# systems-controller.net
KiCad netlist of a schematic drawn in EAGLE
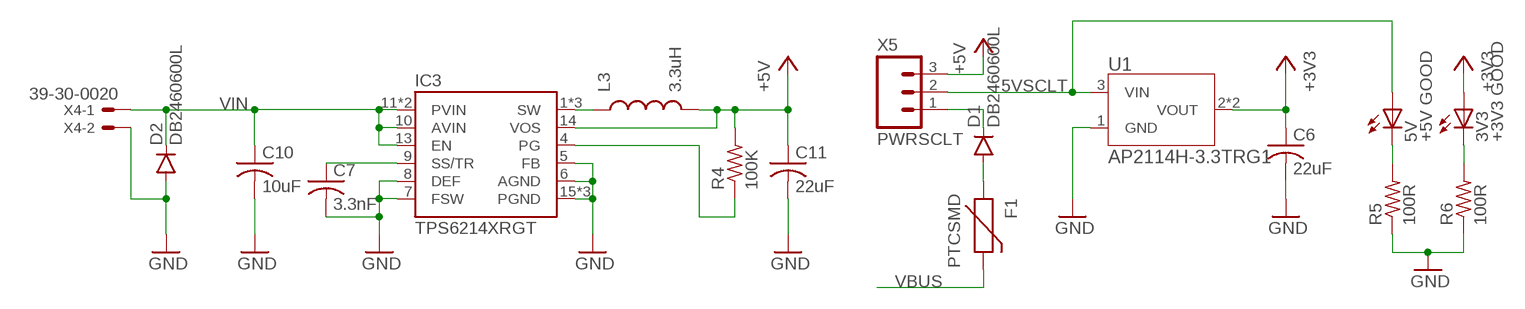
[diagram p0: schematic, sheet 1]
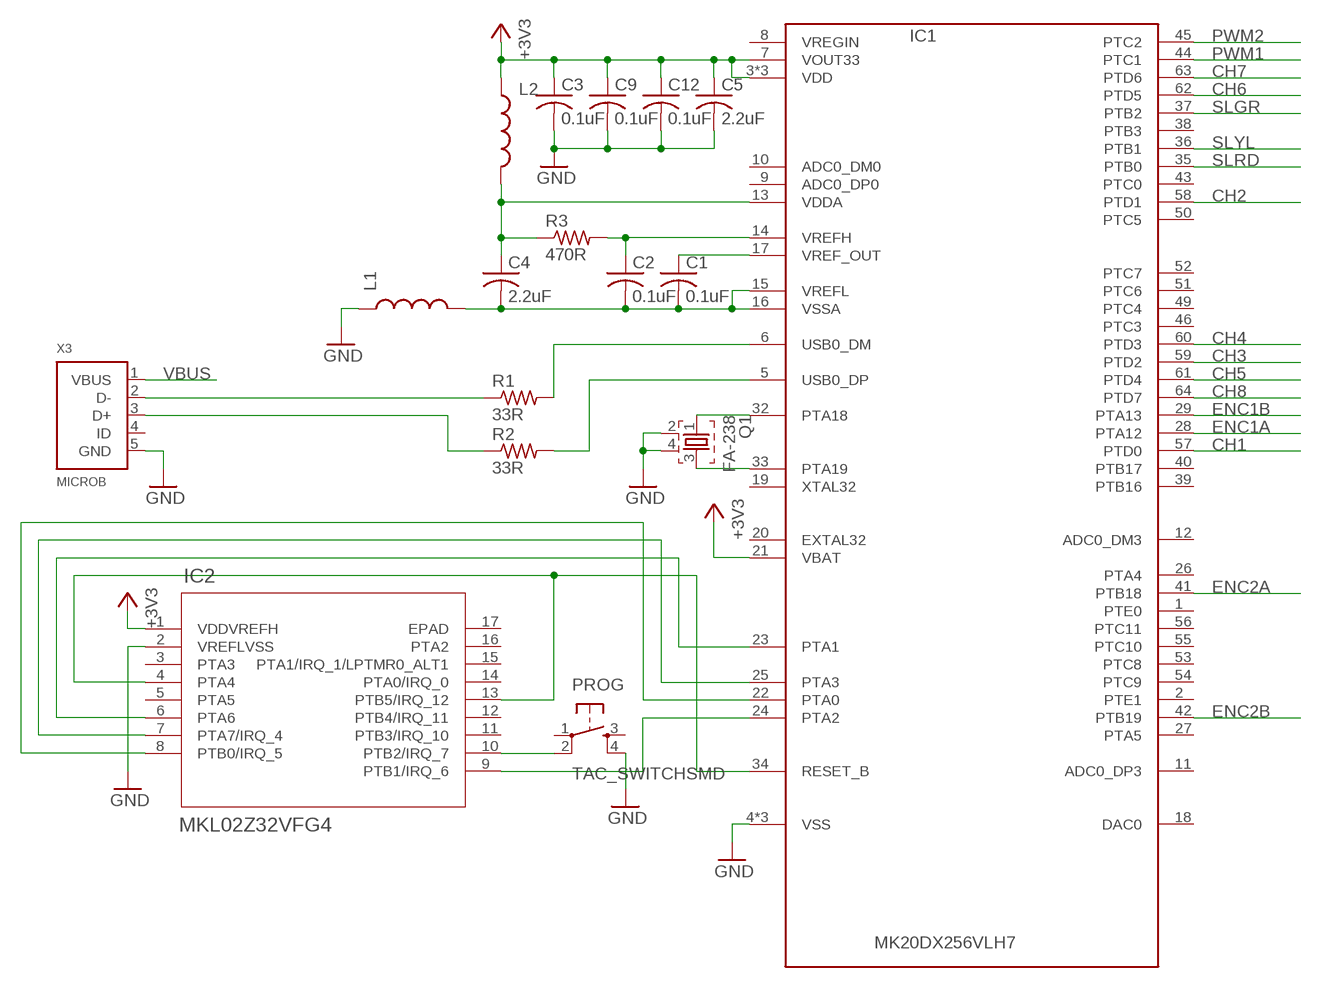
[diagram p1: schematic, sheet 2]
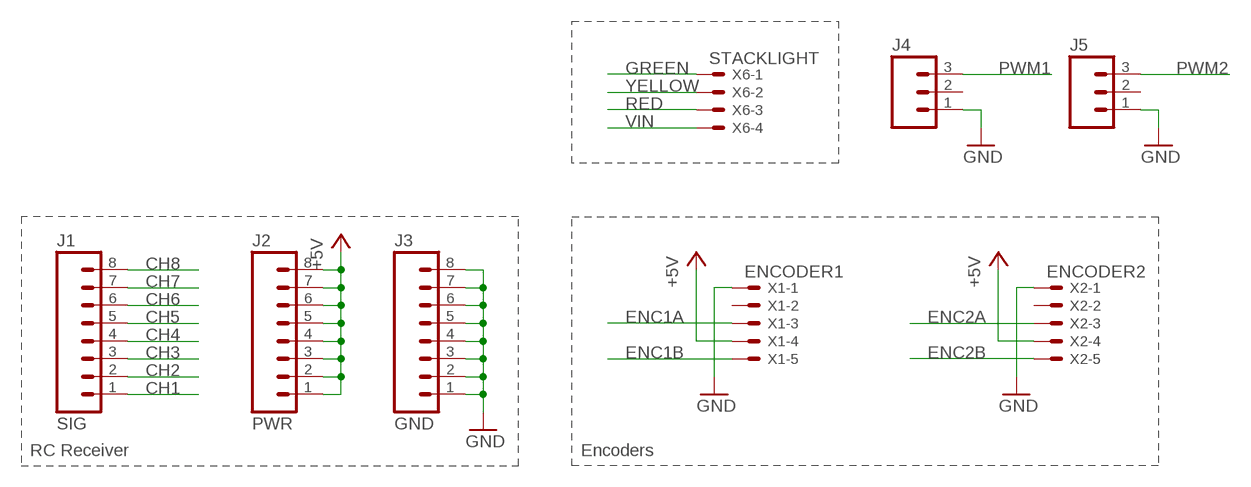
[diagram p2: schematic, sheet 3]
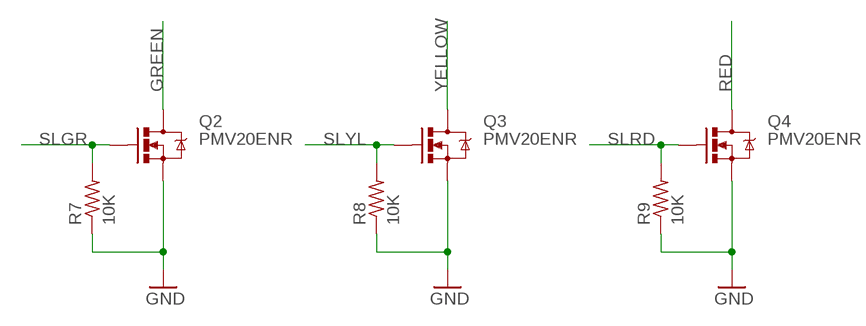
[diagram p3: schematic, sheet 4]

(export (version "E")
  (design (tool "Eeschema 10.0.6"))
  (components
    (comp (ref "3V3")
      (value "+3V3 GOOD")
      (footprint "eagle-import:SML0603")
      (libsource (lib "eagle-import") (part "LEDSML0603"))
    )
    (comp (ref "5V")
      (value "+5V GOOD")
      (footprint "eagle-import:SML0603")
      (libsource (lib "eagle-import") (part "LEDSML0603"))
    )
    (comp (ref "C6")
      (value "22uF")
      (footprint "eagle-import:C0805K")
      (libsource (lib "eagle-import") (part "C-USC0805K"))
    )
    (comp (ref "C7")
      (value "3.3nF")
      (footprint "eagle-import:C0603K")
      (libsource (lib "eagle-import") (part "C-USC0603K"))
    )
    (comp (ref "C10")
      (value "10uF")
      (footprint "eagle-import:C0805K")
      (libsource (lib "eagle-import") (part "C-USC0805K"))
    )
    (comp (ref "C11")
      (value "22uF")
      (footprint "eagle-import:C0805K")
      (libsource (lib "eagle-import") (part "C-USC0805K"))
    )
    (comp (ref "D1")
      (value "DB2460600L")
      (footprint "eagle-import:SOD-128")
      (libsource (lib "eagle-import") (part "DIODESOD128"))
    )
    (comp (ref "D2")
      (value "DB2460600L")
      (footprint "eagle-import:SOD-128")
      (libsource (lib "eagle-import") (part "DIODESOD128"))
    )
    (comp (ref "F1")
      (value "PTCSMD")
      (footprint "eagle-import:PTC-1206")
      (libsource (lib "eagle-import") (part "PTCSMD"))
    )
    (comp (ref "IC3")
      (value "TPS6214XRGT")
      (footprint "eagle-import:16-VQFN")
      (libsource (lib "eagle-import") (part "TPS6214XRGT"))
    )
    (comp (ref "L3")
      (value "3.3uH")
      (footprint "eagle-import:SRN5020")
      (libsource (lib "eagle-import") (part "INDUCTOR-SRN5020"))
    )
    (comp (ref "R4")
      (value "100K")
      (footprint "eagle-import:R0603")
      (libsource (lib "eagle-import") (part "R-US_R0603"))
    )
    (comp (ref "R5")
      (value "100R")
      (footprint "eagle-import:R0603")
      (libsource (lib "eagle-import") (part "R-US_R0603"))
    )
    (comp (ref "R6")
      (value "100R")
      (footprint "eagle-import:R0603")
      (libsource (lib "eagle-import") (part "R-US_R0603"))
    )
    (comp (ref "U1")
      (value "AP2114H-3.3TRG1")
      (footprint "eagle-import:SOT-223")
      (fields (field (name "MANUFACTURER_PART_NUMBER") "ap2114h-3.3trg1"))
      (libsource (lib "eagle-import") (part "AP2114H-3.3TRG1"))
    )
    (comp (ref "X4")
      (value "39-30-0020")
      (footprint "eagle-import:39-30-0020")
      (libsource (lib "eagle-import") (part "39-30-0020"))
    )
    (comp (ref "X5")
      (value "PWRSCLT")
      (footprint "eagle-import:1X03")
      (libsource (lib "eagle-import") (part "M03PTH"))
    )
    (comp (ref "J1")
      (value "SIG")
      (footprint "eagle-import:1X08_ROUND")
      (libsource (lib "eagle-import") (part "M08"))
    )
    (comp (ref "J2")
      (value "PWR")
      (footprint "eagle-import:1X08_ROUND")
      (libsource (lib "eagle-import") (part "M08"))
    )
    (comp (ref "J3")
      (value "GND")
      (footprint "eagle-import:1X08_ROUND")
      (libsource (lib "eagle-import") (part "M08"))
    )
    (comp (ref "J4")
      (value "M03PTH")
      (footprint "eagle-import:1X03")
      (libsource (lib "eagle-import") (part "M03PTH"))
    )
    (comp (ref "J5")
      (value "M03PTH")
      (footprint "eagle-import:1X03")
      (libsource (lib "eagle-import") (part "M03PTH"))
    )
    (comp (ref "X1")
      (value "ENCODER1")
      (footprint "eagle-import:70553-05")
      (libsource (lib "eagle-import") (part "C-GRID-05-70553"))
    )
    (comp (ref "X2")
      (value "ENCODER2")
      (footprint "eagle-import:70553-05")
      (libsource (lib "eagle-import") (part "C-GRID-05-70553"))
    )
    (comp (ref "X6")
      (value "STACKLIGHT")
      (footprint "eagle-import:70553-04")
      (libsource (lib "eagle-import") (part "C-GRID-04-70553"))
    )
    (comp (ref "Q2")
      (value "PMV20ENR")
      (footprint "eagle-import:SOT23-3")
      (libsource (lib "eagle-import") (part "MOSFET-NCHANNELAO3404A"))
    )
    (comp (ref "Q3")
      (value "PMV20ENR")
      (footprint "eagle-import:SOT23-3")
      (libsource (lib "eagle-import") (part "MOSFET-NCHANNELAO3404A"))
    )
    (comp (ref "Q4")
      (value "PMV20ENR")
      (footprint "eagle-import:SOT23-3")
      (libsource (lib "eagle-import") (part "MOSFET-NCHANNELAO3404A"))
    )
    (comp (ref "R7")
      (value "10K")
      (footprint "eagle-import:R0603")
      (libsource (lib "eagle-import") (part "R-US_R0603"))
    )
    (comp (ref "R8")
      (value "10K")
      (footprint "eagle-import:R0603")
      (libsource (lib "eagle-import") (part "R-US_R0603"))
    )
    (comp (ref "R9")
      (value "10K")
      (footprint "eagle-import:R0603")
      (libsource (lib "eagle-import") (part "R-US_R0603"))
    )
    (comp (ref "C1")
      (value "0.1uF")
      (footprint "eagle-import:C0603K")
      (libsource (lib "eagle-import") (part "C-USC0603K"))
    )
    (comp (ref "C2")
      (value "0.1uF")
      (footprint "eagle-import:C0603K")
      (libsource (lib "eagle-import") (part "C-USC0603K"))
    )
    (comp (ref "C3")
      (value "0.1uF")
      (footprint "eagle-import:C0603K")
      (libsource (lib "eagle-import") (part "C-USC0603K"))
    )
    (comp (ref "C4")
      (value "2.2uF")
      (footprint "eagle-import:C0603K")
      (libsource (lib "eagle-import") (part "C-USC0603K"))
    )
    (comp (ref "C5")
      (value "2.2uF")
      (footprint "eagle-import:C0603K")
      (libsource (lib "eagle-import") (part "C-USC0603K"))
    )
    (comp (ref "C9")
      (value "0.1uF")
      (footprint "eagle-import:C0603K")
      (libsource (lib "eagle-import") (part "C-USC0603K"))
    )
    (comp (ref "C12")
      (value "0.1uF")
      (footprint "eagle-import:C0603K")
      (libsource (lib "eagle-import") (part "C-USC0603K"))
    )
    (comp (ref "IC1")
      (value "MK20DX256VLH7")
      (footprint "eagle-import:MK20DX256VLH7")
      (libsource (lib "eagle-import") (part "MK20DX256VLH7"))
    )
    (comp (ref "IC2")
      (value "MKL02Z32VFG4")
      (footprint "eagle-import:QFN-16_3X3X0.65")
      (fields (field (name "MANUFACTURER_PART_NUMBER") "mkl02z32vfg4"))
      (libsource (lib "eagle-import") (part "MKL02Z32VFG4"))
    )
    (comp (ref "L1")
      (value "INDUCTOR30OHM,1.8A")
      (footprint "eagle-import:0603")
      (libsource (lib "eagle-import") (part "INDUCTOR30OHM,1.8A"))
    )
    (comp (ref "L2")
      (value "INDUCTOR30OHM,1.8A")
      (footprint "eagle-import:0603")
      (libsource (lib "eagle-import") (part "INDUCTOR30OHM,1.8A"))
    )
    (comp (ref "PROG")
      (value "TAC_SWITCHSMD")
      (footprint "eagle-import:TACTILE-SWITCH-SMD")
      (libsource (lib "eagle-import") (part "TAC_SWITCHSMD"))
    )
    (comp (ref "Q1")
      (value "FA-238")
      (footprint "eagle-import:FA-238")
      (libsource (lib "eagle-import") (part "FA-238"))
    )
    (comp (ref "R1")
      (value "33R")
      (footprint "eagle-import:R0603")
      (libsource (lib "eagle-import") (part "R-US_R0603"))
    )
    (comp (ref "R2")
      (value "33R")
      (footprint "eagle-import:R0603")
      (libsource (lib "eagle-import") (part "R-US_R0603"))
    )
    (comp (ref "R3")
      (value "470R")
      (footprint "eagle-import:R0603")
      (libsource (lib "eagle-import") (part "R-US_R0603"))
    )
    (comp (ref "X3")
      (value "MICROB")
      (footprint "eagle-import:10118192")
      (libsource (lib "eagle-import") (part "MICROB"))
    )
  )
  (nets
    (net (code "1") (name "+3V3") (class "Default")
      (node (ref "3V3") (pin "A") (pinfunction "A_A") (pintype "passive"))
      (node (ref "C12") (pin "1") (pinfunction "1_1") (pintype "passive"))
      (node (ref "C3") (pin "1") (pinfunction "1_1") (pintype "passive"))
      (node (ref "C5") (pin "1") (pinfunction "1_1") (pintype "passive"))
      (node (ref "C6") (pin "1") (pinfunction "1_1") (pintype "passive"))
      (node (ref "C9") (pin "1") (pinfunction "1_1") (pintype "passive"))
      (node (ref "IC1") (pin "21") (pinfunction "VBAT_21") (pintype "bidirectional"))
      (node (ref "IC1") (pin "3") (pinfunction "VDD_3") (pintype "bidirectional"))
      (node (ref "IC1") (pin "30") (pinfunction "VDD_30") (pintype "bidirectional"))
      (node (ref "IC1") (pin "48") (pinfunction "VDD_48") (pintype "bidirectional"))
      (node (ref "IC1") (pin "7") (pinfunction "VOUT33_7") (pintype "bidirectional"))
      (node (ref "IC2") (pin "1") (pinfunction "VDDVREFH_1") (pintype "power_in"))
      (node (ref "L2") (pin "1") (pinfunction "1_1") (pintype "passive"))
      (node (ref "U1") (pin "2") (pinfunction "VOUT_2") (pintype "output"))
      (node (ref "U1") (pin "4") (pinfunction "VOUT_4") (pintype "output"))
    )
    (net (code "2") (name "+5V") (class "Default")
      (node (ref "C11") (pin "1") (pinfunction "1_1") (pintype "passive"))
      (node (ref "IC3") (pin "14") (pinfunction "VOS_14") (pintype "input"))
      (node (ref "J2") (pin "1") (pinfunction "1_1") (pintype "passive"))
      (node (ref "J2") (pin "2") (pinfunction "2_2") (pintype "passive"))
      (node (ref "J2") (pin "3") (pinfunction "3_3") (pintype "passive"))
      (node (ref "J2") (pin "4") (pinfunction "4_4") (pintype "passive"))
      (node (ref "J2") (pin "5") (pinfunction "5_5") (pintype "passive"))
      (node (ref "J2") (pin "6") (pinfunction "6_6") (pintype "passive"))
      (node (ref "J2") (pin "7") (pinfunction "7_7") (pintype "passive"))
      (node (ref "J2") (pin "8") (pinfunction "8_8") (pintype "passive"))
      (node (ref "L3") (pin "2") (pinfunction "2_2") (pintype "passive"))
      (node (ref "R4") (pin "2") (pinfunction "2_2") (pintype "passive"))
      (node (ref "X1") (pin "4") (pinfunction "S_4") (pintype "passive"))
      (node (ref "X2") (pin "4") (pinfunction "S_4") (pintype "passive"))
      (node (ref "X5") (pin "3") (pinfunction "3_3") (pintype "passive"))
    )
    (net (code "3") (name "5VSCLT") (class "Default")
      (node (ref "5V") (pin "A") (pinfunction "A_A") (pintype "passive"))
      (node (ref "U1") (pin "3") (pinfunction "VIN_3") (pintype "input"))
      (node (ref "X5") (pin "2") (pinfunction "2_2") (pintype "passive"))
    )
    (net (code "4") (name "CH1") (class "Default")
      (node (ref "IC1") (pin "57") (pinfunction "PTD0_57") (pintype "bidirectional"))
      (node (ref "J1") (pin "1") (pinfunction "1_1") (pintype "passive"))
    )
    (net (code "5") (name "CH2") (class "Default")
      (node (ref "IC1") (pin "58") (pinfunction "PTD1_58") (pintype "bidirectional"))
      (node (ref "J1") (pin "2") (pinfunction "2_2") (pintype "passive"))
    )
    (net (code "6") (name "CH3") (class "Default")
      (node (ref "IC1") (pin "59") (pinfunction "PTD2_59") (pintype "bidirectional"))
      (node (ref "J1") (pin "3") (pinfunction "3_3") (pintype "passive"))
    )
    (net (code "7") (name "CH4") (class "Default")
      (node (ref "IC1") (pin "60") (pinfunction "PTD3_60") (pintype "bidirectional"))
      (node (ref "J1") (pin "4") (pinfunction "4_4") (pintype "passive"))
    )
    (net (code "8") (name "CH5") (class "Default")
      (node (ref "IC1") (pin "61") (pinfunction "PTD4_61") (pintype "bidirectional"))
      (node (ref "J1") (pin "5") (pinfunction "5_5") (pintype "passive"))
    )
    (net (code "9") (name "CH6") (class "Default")
      (node (ref "IC1") (pin "62") (pinfunction "PTD5_62") (pintype "bidirectional"))
      (node (ref "J1") (pin "6") (pinfunction "6_6") (pintype "passive"))
    )
    (net (code "10") (name "CH7") (class "Default")
      (node (ref "IC1") (pin "63") (pinfunction "PTD6_63") (pintype "bidirectional"))
      (node (ref "J1") (pin "7") (pinfunction "7_7") (pintype "passive"))
    )
    (net (code "11") (name "CH8") (class "Default")
      (node (ref "IC1") (pin "64") (pinfunction "PTD7_64") (pintype "bidirectional"))
      (node (ref "J1") (pin "8") (pinfunction "8_8") (pintype "passive"))
    )
    (net (code "12") (name "ENC1A") (class "Default")
      (node (ref "IC1") (pin "28") (pinfunction "PTA12_28") (pintype "bidirectional"))
      (node (ref "X1") (pin "3") (pinfunction "S_3") (pintype "passive"))
    )
    (net (code "13") (name "ENC1B") (class "Default")
      (node (ref "IC1") (pin "29") (pinfunction "PTA13_29") (pintype "bidirectional"))
      (node (ref "X1") (pin "5") (pinfunction "S_5") (pintype "passive"))
    )
    (net (code "14") (name "ENC2A") (class "Default")
      (node (ref "IC1") (pin "41") (pinfunction "PTB18_41") (pintype "bidirectional"))
      (node (ref "X2") (pin "3") (pinfunction "S_3") (pintype "passive"))
    )
    (net (code "15") (name "ENC2B") (class "Default")
      (node (ref "IC1") (pin "42") (pinfunction "PTB19_42") (pintype "bidirectional"))
      (node (ref "X2") (pin "5") (pinfunction "S_5") (pintype "passive"))
    )
    (net (code "16") (name "GND") (class "Default")
      (node (ref "C10") (pin "2") (pinfunction "2_2") (pintype "passive"))
      (node (ref "C11") (pin "2") (pinfunction "2_2") (pintype "passive"))
      (node (ref "C12") (pin "2") (pinfunction "2_2") (pintype "passive"))
      (node (ref "C3") (pin "2") (pinfunction "2_2") (pintype "passive"))
      (node (ref "C5") (pin "2") (pinfunction "2_2") (pintype "passive"))
      (node (ref "C6") (pin "2") (pinfunction "2_2") (pintype "passive"))
      (node (ref "C7") (pin "2") (pinfunction "2_2") (pintype "passive"))
      (node (ref "C9") (pin "2") (pinfunction "2_2") (pintype "passive"))
      (node (ref "D2") (pin "A") (pinfunction "A_A") (pintype "passive"))
      (node (ref "IC1") (pin "31") (pinfunction "VSS_31") (pintype "bidirectional"))
      (node (ref "IC1") (pin "4") (pinfunction "VSS_4") (pintype "bidirectional"))
      (node (ref "IC1") (pin "47") (pinfunction "VSS_47") (pintype "bidirectional"))
      (node (ref "IC2") (pin "2") (pinfunction "VREFLVSS_2") (pintype "power_in"))
      (node (ref "IC3") (pin "15") (pinfunction "PGND_15") (pintype "power_in"))
      (node (ref "IC3") (pin "16") (pinfunction "PGND_16") (pintype "power_in"))
      (node (ref "IC3") (pin "5") (pinfunction "FB_5") (pintype "input"))
      (node (ref "IC3") (pin "6") (pinfunction "AGND_6") (pintype "input"))
      (node (ref "IC3") (pin "7") (pinfunction "FSW_7") (pintype "input"))
      (node (ref "IC3") (pin "8") (pinfunction "DEF_8") (pintype "input"))
      (node (ref "IC3") (pin "PAD") (pinfunction "PGND_PAD") (pintype "power_in"))
      (node (ref "J3") (pin "1") (pinfunction "1_1") (pintype "passive"))
      (node (ref "J3") (pin "2") (pinfunction "2_2") (pintype "passive"))
      (node (ref "J3") (pin "3") (pinfunction "3_3") (pintype "passive"))
      (node (ref "J3") (pin "4") (pinfunction "4_4") (pintype "passive"))
      (node (ref "J3") (pin "5") (pinfunction "5_5") (pintype "passive"))
      (node (ref "J3") (pin "6") (pinfunction "6_6") (pintype "passive"))
      (node (ref "J3") (pin "7") (pinfunction "7_7") (pintype "passive"))
      (node (ref "J3") (pin "8") (pinfunction "8_8") (pintype "passive"))
      (node (ref "J4") (pin "1") (pinfunction "1_1") (pintype "passive"))
      (node (ref "J5") (pin "1") (pinfunction "1_1") (pintype "passive"))
      (node (ref "L1") (pin "1") (pinfunction "1_1") (pintype "passive"))
      (node (ref "PROG") (pin "4") (pinfunction "4_4") (pintype "passive"))
      (node (ref "Q1") (pin "2") (pinfunction "2_2") (pintype "passive"))
      (node (ref "Q1") (pin "4") (pinfunction "4_4") (pintype "passive"))
      (node (ref "Q2") (pin "2") (pinfunction "S_2") (pintype "passive"))
      (node (ref "Q3") (pin "2") (pinfunction "S_2") (pintype "passive"))
      (node (ref "Q4") (pin "2") (pinfunction "S_2") (pintype "passive"))
      (node (ref "R5") (pin "1") (pinfunction "1_1") (pintype "passive"))
      (node (ref "R6") (pin "1") (pinfunction "1_1") (pintype "passive"))
      (node (ref "R7") (pin "1") (pinfunction "1_1") (pintype "passive"))
      (node (ref "R8") (pin "1") (pinfunction "1_1") (pintype "passive"))
      (node (ref "R9") (pin "1") (pinfunction "1_1") (pintype "passive"))
      (node (ref "U1") (pin "1") (pinfunction "GND_1") (pintype "power_in"))
      (node (ref "X1") (pin "1") (pinfunction "S_1") (pintype "passive"))
      (node (ref "X2") (pin "1") (pinfunction "S_1") (pintype "passive"))
      (node (ref "X3") (pin "5") (pinfunction "GND_5") (pintype "bidirectional"))
      (node (ref "X4") (pin "2") (pinfunction "S_2") (pintype "passive"))
    )
    (net (code "17") (name "GREEN") (class "Default")
      (node (ref "Q2") (pin "3") (pinfunction "D_3") (pintype "passive"))
      (node (ref "X6") (pin "1") (pinfunction "S_1") (pintype "passive"))
    )
    (net (code "18") (name "Net-(3V3-PadC)") (class "Default")
      (node (ref "3V3") (pin "C") (pinfunction "C_C") (pintype "passive"))
      (node (ref "R6") (pin "2") (pinfunction "2_2") (pintype "passive"))
    )
    (net (code "19") (name "Net-(5V-PadC)") (class "Default")
      (node (ref "5V") (pin "C") (pinfunction "C_C") (pintype "passive"))
      (node (ref "R5") (pin "2") (pinfunction "2_2") (pintype "passive"))
    )
    (net (code "20") (name "Net-(D1-PadA)") (class "Default")
      (node (ref "D1") (pin "A") (pinfunction "A_A") (pintype "passive"))
      (node (ref "F1") (pin "1") (pinfunction "1_1") (pintype "bidirectional"))
    )
    (net (code "21") (name "Net-(D1-PadC)") (class "Default")
      (node (ref "D1") (pin "C") (pinfunction "C_C") (pintype "passive"))
      (node (ref "X5") (pin "1") (pinfunction "1_1") (pintype "passive"))
    )
    (net (code "22") (name "Net-(IC1-PTA0)") (class "Default")
      (node (ref "IC1") (pin "22") (pinfunction "PTA0_22") (pintype "bidirectional"))
      (node (ref "IC2") (pin "8") (pinfunction "PTB0/IRQ_5_8") (pintype "bidirectional"))
    )
    (net (code "23") (name "Net-(IC1-PTA1)") (class "Default")
      (node (ref "IC1") (pin "23") (pinfunction "PTA1_23") (pintype "bidirectional"))
      (node (ref "IC2") (pin "6") (pinfunction "PTA6_6") (pintype "bidirectional"))
    )
    (net (code "24") (name "Net-(IC1-PTA2)") (class "Default")
      (node (ref "IC1") (pin "24") (pinfunction "PTA2_24") (pintype "bidirectional"))
      (node (ref "IC2") (pin "9") (pinfunction "PTB1/IRQ_6_9") (pintype "bidirectional"))
    )
    (net (code "25") (name "Net-(IC1-PTA3)") (class "Default")
      (node (ref "IC1") (pin "25") (pinfunction "PTA3_25") (pintype "bidirectional"))
      (node (ref "IC2") (pin "7") (pinfunction "PTA7/IRQ_4_7") (pintype "bidirectional"))
    )
    (net (code "26") (name "Net-(IC1-PTA18)") (class "Default")
      (node (ref "IC1") (pin "32") (pinfunction "PTA18_32") (pintype "bidirectional"))
      (node (ref "Q1") (pin "1") (pinfunction "1_1") (pintype "passive"))
    )
    (net (code "27") (name "Net-(IC1-PTA19)") (class "Default")
      (node (ref "IC1") (pin "33") (pinfunction "PTA19_33") (pintype "bidirectional"))
      (node (ref "Q1") (pin "3") (pinfunction "3_3") (pintype "passive"))
    )
    (net (code "28") (name "Net-(IC1-RESET_B)") (class "Default")
      (node (ref "IC1") (pin "34") (pinfunction "RESET_B_34") (pintype "bidirectional"))
      (node (ref "IC2") (pin "13") (pinfunction "PTB5/IRQ_12_13") (pintype "bidirectional"))
      (node (ref "IC2") (pin "4") (pinfunction "PTA4_4") (pintype "bidirectional"))
    )
    (net (code "29") (name "Net-(IC1-USB0_DM)") (class "Default")
      (node (ref "IC1") (pin "6") (pinfunction "USB0_DM_6") (pintype "bidirectional"))
      (node (ref "R1") (pin "2") (pinfunction "2_2") (pintype "passive"))
    )
    (net (code "30") (name "Net-(IC1-USB0_DP)") (class "Default")
      (node (ref "IC1") (pin "5") (pinfunction "USB0_DP_5") (pintype "bidirectional"))
      (node (ref "R2") (pin "2") (pinfunction "2_2") (pintype "passive"))
    )
    (net (code "31") (name "Net-(IC1-VDDA)") (class "Default")
      (node (ref "C4") (pin "1") (pinfunction "1_1") (pintype "passive"))
      (node (ref "IC1") (pin "13") (pinfunction "VDDA_13") (pintype "bidirectional"))
      (node (ref "L2") (pin "2") (pinfunction "2_2") (pintype "passive"))
      (node (ref "R3") (pin "1") (pinfunction "1_1") (pintype "passive"))
    )
    (net (code "32") (name "Net-(IC1-VREFH)") (class "Default")
      (node (ref "C2") (pin "1") (pinfunction "1_1") (pintype "passive"))
      (node (ref "IC1") (pin "14") (pinfunction "VREFH_14") (pintype "bidirectional"))
      (node (ref "R3") (pin "2") (pinfunction "2_2") (pintype "passive"))
    )
    (net (code "33") (name "Net-(IC1-VREFL)") (class "Default")
      (node (ref "C1") (pin "2") (pinfunction "2_2") (pintype "passive"))
      (node (ref "C2") (pin "2") (pinfunction "2_2") (pintype "passive"))
      (node (ref "C4") (pin "2") (pinfunction "2_2") (pintype "passive"))
      (node (ref "IC1") (pin "15") (pinfunction "VREFL_15") (pintype "bidirectional"))
      (node (ref "IC1") (pin "16") (pinfunction "VSSA_16") (pintype "bidirectional"))
      (node (ref "L1") (pin "2") (pinfunction "2_2") (pintype "passive"))
    )
    (net (code "34") (name "Net-(IC1-VREF_OUT)") (class "Default")
      (node (ref "C1") (pin "1") (pinfunction "1_1") (pintype "passive"))
      (node (ref "IC1") (pin "17") (pinfunction "VREF_OUT_17") (pintype "bidirectional"))
    )
    (net (code "35") (name "Net-(IC2-PTB2{slash}IRQ_7)") (class "Default")
      (node (ref "IC2") (pin "10") (pinfunction "PTB2/IRQ_7_10") (pintype "bidirectional"))
      (node (ref "PROG") (pin "2") (pinfunction "2_2") (pintype "passive"))
    )
    (net (code "36") (name "Net-(IC3-PG)") (class "Default")
      (node (ref "IC3") (pin "4") (pinfunction "PG_4") (pintype "output"))
      (node (ref "R4") (pin "1") (pinfunction "1_1") (pintype "passive"))
    )
    (net (code "37") (name "Net-(IC3-SS{slash}TR)") (class "Default")
      (node (ref "C7") (pin "1") (pinfunction "1_1") (pintype "passive"))
      (node (ref "IC3") (pin "9") (pinfunction "SS/TR_9") (pintype "input"))
    )
    (net (code "38") (name "Net-(IC3-SW-Pad1)") (class "Default")
      (node (ref "IC3") (pin "1") (pinfunction "SW_1") (pintype "output"))
      (node (ref "IC3") (pin "2") (pinfunction "SW_2") (pintype "output"))
      (node (ref "IC3") (pin "3") (pinfunction "SW_3") (pintype "output"))
      (node (ref "L3") (pin "1") (pinfunction "1_1") (pintype "passive"))
    )
    (net (code "39") (name "Net-(X3-D+)") (class "Default")
      (node (ref "R2") (pin "1") (pinfunction "1_1") (pintype "passive"))
      (node (ref "X3") (pin "3") (pinfunction "D+_3") (pintype "bidirectional"))
    )
    (net (code "40") (name "Net-(X3-D-)") (class "Default")
      (node (ref "R1") (pin "1") (pinfunction "1_1") (pintype "passive"))
      (node (ref "X3") (pin "2") (pinfunction "D-_2") (pintype "bidirectional"))
    )
    (net (code "41") (name "PWM1") (class "Default")
      (node (ref "IC1") (pin "44") (pinfunction "PTC1_44") (pintype "bidirectional"))
      (node (ref "J4") (pin "3") (pinfunction "3_3") (pintype "passive"))
    )
    (net (code "42") (name "PWM2") (class "Default")
      (node (ref "IC1") (pin "45") (pinfunction "PTC2_45") (pintype "bidirectional"))
      (node (ref "J5") (pin "3") (pinfunction "3_3") (pintype "passive"))
    )
    (net (code "43") (name "RED") (class "Default")
      (node (ref "Q4") (pin "3") (pinfunction "D_3") (pintype "passive"))
      (node (ref "X6") (pin "3") (pinfunction "S_3") (pintype "passive"))
    )
    (net (code "44") (name "SLGR") (class "Default")
      (node (ref "IC1") (pin "37") (pinfunction "PTB2_37") (pintype "bidirectional"))
      (node (ref "Q2") (pin "1") (pinfunction "G_1") (pintype "passive"))
      (node (ref "R7") (pin "2") (pinfunction "2_2") (pintype "passive"))
    )
    (net (code "45") (name "SLRD") (class "Default")
      (node (ref "IC1") (pin "35") (pinfunction "PTB0_35") (pintype "bidirectional"))
      (node (ref "Q4") (pin "1") (pinfunction "G_1") (pintype "passive"))
      (node (ref "R9") (pin "2") (pinfunction "2_2") (pintype "passive"))
    )
    (net (code "46") (name "SLYL") (class "Default")
      (node (ref "IC1") (pin "36") (pinfunction "PTB1_36") (pintype "bidirectional"))
      (node (ref "Q3") (pin "1") (pinfunction "G_1") (pintype "passive"))
      (node (ref "R8") (pin "2") (pinfunction "2_2") (pintype "passive"))
    )
    (net (code "47") (name "VBUS") (class "Default")
      (node (ref "F1") (pin "2") (pinfunction "2_2") (pintype "bidirectional"))
      (node (ref "X3") (pin "1") (pinfunction "VBUS_1") (pintype "bidirectional"))
    )
    (net (code "48") (name "VIN") (class "Default")
      (node (ref "C10") (pin "1") (pinfunction "1_1") (pintype "passive"))
      (node (ref "D2") (pin "C") (pinfunction "C_C") (pintype "passive"))
      (node (ref "IC3") (pin "10") (pinfunction "AVIN_10") (pintype "input"))
      (node (ref "IC3") (pin "11") (pinfunction "PVIN_11") (pintype "input"))
      (node (ref "IC3") (pin "12") (pinfunction "PVIN_12") (pintype "input"))
      (node (ref "IC3") (pin "13") (pinfunction "EN_13") (pintype "input"))
      (node (ref "X4") (pin "1") (pinfunction "S_1") (pintype "passive"))
      (node (ref "X6") (pin "4") (pinfunction "S_4") (pintype "passive"))
    )
    (net (code "49") (name "YELLOW") (class "Default")
      (node (ref "Q3") (pin "3") (pinfunction "D_3") (pintype "passive"))
      (node (ref "X6") (pin "2") (pinfunction "S_2") (pintype "passive"))
    )
    (net (code "50") (name "unconnected-(IC1-ADC0_DM0-Pad10)") (class "Default")
      (node (ref "IC1") (pin "10") (pinfunction "ADC0_DM0_10") (pintype "bidirectional"))
    )
    (net (code "51") (name "unconnected-(IC1-ADC0_DM3-Pad12)") (class "Default")
      (node (ref "IC1") (pin "12") (pinfunction "ADC0_DM3_12") (pintype "bidirectional"))
    )
    (net (code "52") (name "unconnected-(IC1-ADC0_DP0-Pad9)") (class "Default")
      (node (ref "IC1") (pin "9") (pinfunction "ADC0_DP0_9") (pintype "bidirectional"))
    )
    (net (code "53") (name "unconnected-(IC1-ADC0_DP3-Pad11)") (class "Default")
      (node (ref "IC1") (pin "11") (pinfunction "ADC0_DP3_11") (pintype "bidirectional"))
    )
    (net (code "54") (name "unconnected-(IC1-DAC0-Pad18)") (class "Default")
      (node (ref "IC1") (pin "18") (pinfunction "DAC0_18") (pintype "bidirectional"))
    )
    (net (code "55") (name "unconnected-(IC1-EXTAL32-Pad20)") (class "Default")
      (node (ref "IC1") (pin "20") (pinfunction "EXTAL32_20") (pintype "bidirectional"))
    )
    (net (code "56") (name "unconnected-(IC1-PTA4-Pad26)") (class "Default")
      (node (ref "IC1") (pin "26") (pinfunction "PTA4_26") (pintype "bidirectional"))
    )
    (net (code "57") (name "unconnected-(IC1-PTA5-Pad27)") (class "Default")
      (node (ref "IC1") (pin "27") (pinfunction "PTA5_27") (pintype "bidirectional"))
    )
    (net (code "58") (name "unconnected-(IC1-PTB3-Pad38)") (class "Default")
      (node (ref "IC1") (pin "38") (pinfunction "PTB3_38") (pintype "bidirectional"))
    )
    (net (code "59") (name "unconnected-(IC1-PTB16-Pad39)") (class "Default")
      (node (ref "IC1") (pin "39") (pinfunction "PTB16_39") (pintype "bidirectional"))
    )
    (net (code "60") (name "unconnected-(IC1-PTB17-Pad40)") (class "Default")
      (node (ref "IC1") (pin "40") (pinfunction "PTB17_40") (pintype "bidirectional"))
    )
    (net (code "61") (name "unconnected-(IC1-PTC0-Pad43)") (class "Default")
      (node (ref "IC1") (pin "43") (pinfunction "PTC0_43") (pintype "bidirectional"))
    )
    (net (code "62") (name "unconnected-(IC1-PTC3-Pad46)") (class "Default")
      (node (ref "IC1") (pin "46") (pinfunction "PTC3_46") (pintype "bidirectional"))
    )
    (net (code "63") (name "unconnected-(IC1-PTC4-Pad49)") (class "Default")
      (node (ref "IC1") (pin "49") (pinfunction "PTC4_49") (pintype "bidirectional"))
    )
    (net (code "64") (name "unconnected-(IC1-PTC5-Pad50)") (class "Default")
      (node (ref "IC1") (pin "50") (pinfunction "PTC5_50") (pintype "bidirectional"))
    )
    (net (code "65") (name "unconnected-(IC1-PTC6-Pad51)") (class "Default")
      (node (ref "IC1") (pin "51") (pinfunction "PTC6_51") (pintype "bidirectional"))
    )
    (net (code "66") (name "unconnected-(IC1-PTC7-Pad52)") (class "Default")
      (node (ref "IC1") (pin "52") (pinfunction "PTC7_52") (pintype "bidirectional"))
    )
    (net (code "67") (name "unconnected-(IC1-PTC8-Pad53)") (class "Default")
      (node (ref "IC1") (pin "53") (pinfunction "PTC8_53") (pintype "bidirectional"))
    )
    (net (code "68") (name "unconnected-(IC1-PTC9-Pad54)") (class "Default")
      (node (ref "IC1") (pin "54") (pinfunction "PTC9_54") (pintype "bidirectional"))
    )
    (net (code "69") (name "unconnected-(IC1-PTC10-Pad55)") (class "Default")
      (node (ref "IC1") (pin "55") (pinfunction "PTC10_55") (pintype "bidirectional"))
    )
    (net (code "70") (name "unconnected-(IC1-PTC11-Pad56)") (class "Default")
      (node (ref "IC1") (pin "56") (pinfunction "PTC11_56") (pintype "bidirectional"))
    )
    (net (code "71") (name "unconnected-(IC1-PTE0-Pad1)") (class "Default")
      (node (ref "IC1") (pin "1") (pinfunction "PTE0_1") (pintype "bidirectional"))
    )
    (net (code "72") (name "unconnected-(IC1-PTE1-Pad2)") (class "Default")
      (node (ref "IC1") (pin "2") (pinfunction "PTE1_2") (pintype "bidirectional"))
    )
    (net (code "73") (name "unconnected-(IC1-VREGIN-Pad8)") (class "Default")
      (node (ref "IC1") (pin "8") (pinfunction "VREGIN_8") (pintype "bidirectional"))
    )
    (net (code "74") (name "unconnected-(IC1-XTAL32-Pad19)") (class "Default")
      (node (ref "IC1") (pin "19") (pinfunction "XTAL32_19") (pintype "bidirectional"))
    )
    (net (code "75") (name "unconnected-(IC2-EPAD-Pad17)") (class "Default")
      (node (ref "IC2") (pin "17") (pinfunction "EPAD_17") (pintype "passive"))
    )
    (net (code "76") (name "unconnected-(IC2-PTA0{slash}IRQ_0-Pad14)") (class "Default")
      (node (ref "IC2") (pin "14") (pinfunction "PTA0/IRQ_0_14") (pintype "bidirectional"))
    )
    (net (code "77") (name "unconnected-(IC2-PTA1{slash}IRQ_1{slash}LPTMR0_ALT1-Pad15)") (class "Default")
      (node (ref "IC2") (pin "15") (pinfunction "PTA1/IRQ_1/LPTMR0_ALT1_15") (pintype "bidirectional"))
    )
    (net (code "78") (name "unconnected-(IC2-PTA2-Pad16)") (class "Default")
      (node (ref "IC2") (pin "16") (pinfunction "PTA2_16") (pintype "bidirectional"))
    )
    (net (code "79") (name "unconnected-(IC2-PTA3-Pad3)") (class "Default")
      (node (ref "IC2") (pin "3") (pinfunction "PTA3_3") (pintype "bidirectional"))
    )
    (net (code "80") (name "unconnected-(IC2-PTA5-Pad5)") (class "Default")
      (node (ref "IC2") (pin "5") (pinfunction "PTA5_5") (pintype "bidirectional"))
    )
    (net (code "81") (name "unconnected-(IC2-PTB3{slash}IRQ_10-Pad11)") (class "Default")
      (node (ref "IC2") (pin "11") (pinfunction "PTB3/IRQ_10_11") (pintype "bidirectional"))
    )
    (net (code "82") (name "unconnected-(IC2-PTB4{slash}IRQ_11-Pad12)") (class "Default")
      (node (ref "IC2") (pin "12") (pinfunction "PTB4/IRQ_11_12") (pintype "bidirectional"))
    )
    (net (code "83") (name "unconnected-(J4-Pad2)") (class "Default")
      (node (ref "J4") (pin "2") (pinfunction "2_2") (pintype "passive"))
    )
    (net (code "84") (name "unconnected-(J5-Pad2)") (class "Default")
      (node (ref "J5") (pin "2") (pinfunction "2_2") (pintype "passive"))
    )
    (net (code "85") (name "unconnected-(PROG-Pad1)") (class "Default")
      (node (ref "PROG") (pin "1") (pinfunction "1_1") (pintype "passive"))
    )
    (net (code "86") (name "unconnected-(PROG-Pad3)") (class "Default")
      (node (ref "PROG") (pin "3") (pinfunction "3_3") (pintype "passive"))
    )
    (net (code "87") (name "unconnected-(X1B-S-Pad2)") (class "Default")
      (node (ref "X1") (pin "2") (pinfunction "S_2") (pintype "passive"))
    )
    (net (code "88") (name "unconnected-(X2B-S-Pad2)") (class "Default")
      (node (ref "X2") (pin "2") (pinfunction "S_2") (pintype "passive"))
    )
    (net (code "89") (name "unconnected-(X3-ID-Pad4)") (class "Default")
      (node (ref "X3") (pin "4") (pinfunction "ID_4") (pintype "bidirectional"))
    )
  )
)
